# M8399A.net
KiCad netlist of a schematic drawn in EAGLE
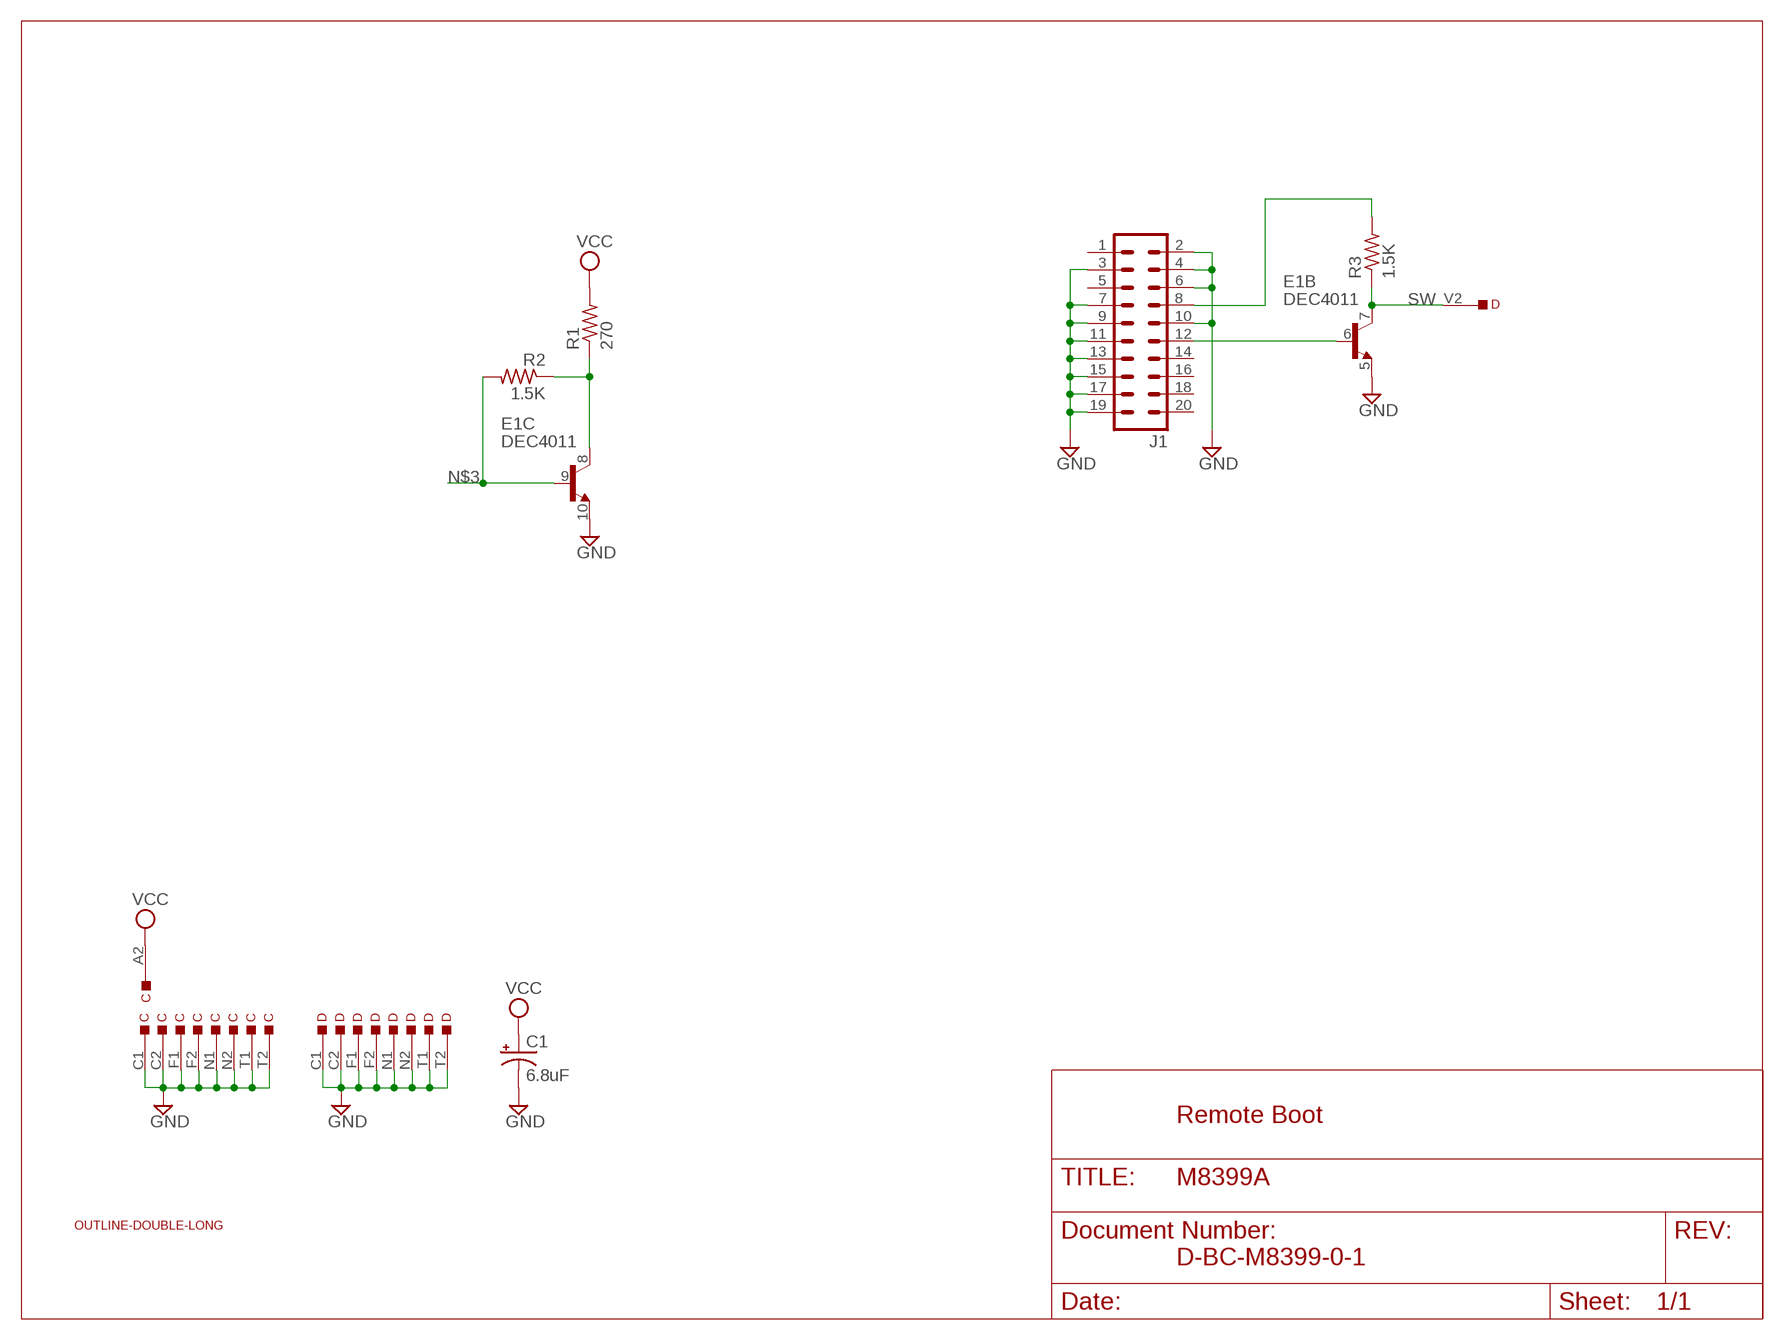
[diagram p0: schematic, sheet 1]

(export (version "E")
  (design (tool "Eeschema 10.0.6"))
  (components
    (comp (ref "C")
      (value "EDGE-TOP")
      (footprint "eagle-import:EDGE-CON2")
      (libsource (lib "eagle-import") (part "EDGE-TOP"))
    )
    (comp (ref "C1")
      (value "6.8uF")
      (footprint "eagle-import:E12-8")
      (libsource (lib "eagle-import") (part "CPOL-USE20-8AXIAL"))
    )
    (comp (ref "D")
      (value "EDGE-TOP")
      (footprint "eagle-import:EDGE-CON2")
      (libsource (lib "eagle-import") (part "EDGE-TOP"))
    )
    (comp (ref "E1")
      (value "DEC4011")
      (footprint "eagle-import:DIL14")
      (libsource (lib "eagle-import") (part "DEC4011"))
    )
    (comp (ref "J1")
      (value "20H")
      (footprint "eagle-import:20H")
      (libsource (lib "eagle-import") (part "20H"))
    )
    (comp (ref "R1")
      (value "270")
      (footprint "eagle-import:0207_10")
      (libsource (lib "eagle-import") (part "R-US_0207/10"))
    )
    (comp (ref "R2")
      (value "1.5K")
      (footprint "eagle-import:0207_10")
      (libsource (lib "eagle-import") (part "R-US_0207/10"))
    )
    (comp (ref "R3")
      (value "1.5K")
      (footprint "eagle-import:0207_10")
      (libsource (lib "eagle-import") (part "R-US_0207/10"))
    )
    (comp (ref "U$1")
      (value "OUTLINE-DOUBLE-LONG")
      (footprint "eagle-import:DOUBLE-LONG")
      (libsource (lib "eagle-import") (part "OUTLINE-DOUBLE-LONG"))
    )
  )
  (nets
    (net (code "1") (name "/N$3") (class "Default")
      (node (ref "E1") (pin "9") (pinfunction "B_9") (pintype "passive"))
      (node (ref "R2") (pin "2") (pinfunction "2_2") (pintype "passive"))
    )
    (net (code "2") (name "/SW") (class "Default")
      (node (ref "D") (pin "V2") (pinfunction "P_V2") (pintype "passive"))
      (node (ref "E1") (pin "7") (pinfunction "C_7") (pintype "passive"))
      (node (ref "R3") (pin "1") (pinfunction "1_1") (pintype "passive"))
    )
    (net (code "3") (name "GND") (class "Default")
      (node (ref "C") (pin "C1") (pinfunction "P_C1") (pintype "passive"))
      (node (ref "C") (pin "C2") (pinfunction "P_C2") (pintype "passive"))
      (node (ref "C") (pin "F1") (pinfunction "P_F1") (pintype "passive"))
      (node (ref "C") (pin "F2") (pinfunction "P_F2") (pintype "passive"))
      (node (ref "C") (pin "N1") (pinfunction "P_N1") (pintype "passive"))
      (node (ref "C") (pin "N2") (pinfunction "P_N2") (pintype "passive"))
      (node (ref "C") (pin "T1") (pinfunction "P_T1") (pintype "passive"))
      (node (ref "C") (pin "T2") (pinfunction "P_T2") (pintype "passive"))
      (node (ref "C1") (pin "-") (pinfunction "-_-") (pintype "passive"))
      (node (ref "D") (pin "C1") (pinfunction "P_C1") (pintype "passive"))
      (node (ref "D") (pin "C2") (pinfunction "P_C2") (pintype "passive"))
      (node (ref "D") (pin "F1") (pinfunction "P_F1") (pintype "passive"))
      (node (ref "D") (pin "F2") (pinfunction "P_F2") (pintype "passive"))
      (node (ref "D") (pin "N1") (pinfunction "P_N1") (pintype "passive"))
      (node (ref "D") (pin "N2") (pinfunction "P_N2") (pintype "passive"))
      (node (ref "D") (pin "T1") (pinfunction "P_T1") (pintype "passive"))
      (node (ref "D") (pin "T2") (pinfunction "P_T2") (pintype "passive"))
      (node (ref "E1") (pin "10") (pinfunction "E_10") (pintype "passive"))
      (node (ref "E1") (pin "5") (pinfunction "E_5") (pintype "passive"))
      (node (ref "J1") (pin "10") (pinfunction "10_10") (pintype "passive"))
      (node (ref "J1") (pin "11") (pinfunction "11_11") (pintype "passive"))
      (node (ref "J1") (pin "13") (pinfunction "13_13") (pintype "passive"))
      (node (ref "J1") (pin "15") (pinfunction "15_15") (pintype "passive"))
      (node (ref "J1") (pin "17") (pinfunction "17_17") (pintype "passive"))
      (node (ref "J1") (pin "19") (pinfunction "19_19") (pintype "passive"))
      (node (ref "J1") (pin "2") (pinfunction "2_2") (pintype "passive"))
      (node (ref "J1") (pin "3") (pinfunction "3_3") (pintype "passive"))
      (node (ref "J1") (pin "4") (pinfunction "4_4") (pintype "passive"))
      (node (ref "J1") (pin "6") (pinfunction "6_6") (pintype "passive"))
      (node (ref "J1") (pin "7") (pinfunction "7_7") (pintype "passive"))
      (node (ref "J1") (pin "9") (pinfunction "9_9") (pintype "passive"))
    )
    (net (code "4") (name "Net-(E1B-B)") (class "Default")
      (node (ref "E1") (pin "6") (pinfunction "B_6") (pintype "passive"))
      (node (ref "J1") (pin "12") (pinfunction "12_12") (pintype "passive"))
    )
    (net (code "5") (name "Net-(E1C-C)") (class "Default")
      (node (ref "E1") (pin "8") (pinfunction "C_8") (pintype "passive"))
      (node (ref "R1") (pin "1") (pinfunction "1_1") (pintype "passive"))
      (node (ref "R2") (pin "1") (pinfunction "1_1") (pintype "passive"))
    )
    (net (code "6") (name "Net-(J1-Pad8)") (class "Default")
      (node (ref "J1") (pin "8") (pinfunction "8_8") (pintype "passive"))
      (node (ref "R3") (pin "2") (pinfunction "2_2") (pintype "passive"))
    )
    (net (code "7") (name "VCC") (class "Default")
      (node (ref "C") (pin "A2") (pinfunction "P_A2") (pintype "passive"))
      (node (ref "C1") (pin "+") (pinfunction "+_+") (pintype "passive"))
      (node (ref "R1") (pin "2") (pinfunction "2_2") (pintype "passive"))
    )
    (net (code "8") (name "unconnected-(J1-Pad1)") (class "Default")
      (node (ref "J1") (pin "1") (pinfunction "1_1") (pintype "passive"))
    )
    (net (code "9") (name "unconnected-(J1-Pad5)") (class "Default")
      (node (ref "J1") (pin "5") (pinfunction "5_5") (pintype "passive"))
    )
    (net (code "10") (name "unconnected-(J1-Pad14)") (class "Default")
      (node (ref "J1") (pin "14") (pinfunction "14_14") (pintype "passive"))
    )
    (net (code "11") (name "unconnected-(J1-Pad16)") (class "Default")
      (node (ref "J1") (pin "16") (pinfunction "16_16") (pintype "passive"))
    )
    (net (code "12") (name "unconnected-(J1-Pad18)") (class "Default")
      (node (ref "J1") (pin "18") (pinfunction "18_18") (pintype "passive"))
    )
    (net (code "13") (name "unconnected-(J1-Pad20)") (class "Default")
      (node (ref "J1") (pin "20") (pinfunction "20_20") (pintype "passive"))
    )
  )
)
